# Tube_Board.net
KiCad netlist of a schematic drawn in EAGLE
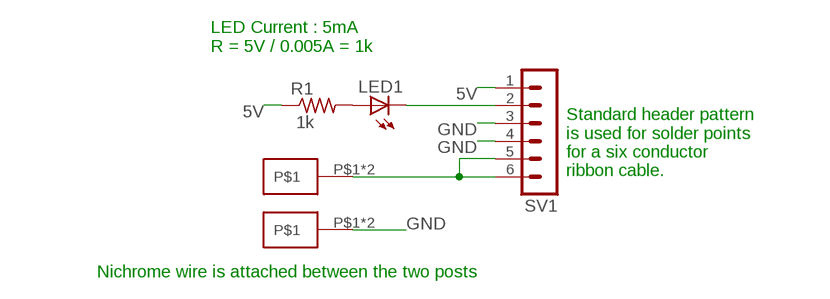
[diagram p0: schematic, sheet 1]

(export (version "E")
  (design (tool "Eeschema 10.0.6"))
  (components
    (comp (ref "LED1")
      (value "LED_ESML0603")
      (footprint "eagle-import:LED_SML0603")
      (libsource (lib "eagle-import") (part "LED_ESML0603"))
    )
    (comp (ref "R1")
      (value "R-US_R0603")
      (footprint "eagle-import:R0603")
      (fields (field (name "R1") "1k"))
      (libsource (lib "eagle-import") (part "R-US_R0603"))
    )
    (comp (ref "SV1")
      (value "MA06-1")
      (footprint "eagle-import:MA06-1")
      (libsource (lib "eagle-import") (part "MA06-1"))
    )
    (comp (ref "U$1")
      (value "A29938CT")
      (footprint "eagle-import:A29938CT")
      (libsource (lib "eagle-import") (part "A29938CT"))
    )
    (comp (ref "U$2")
      (value "A29938CT")
      (footprint "eagle-import:A29938CT")
      (libsource (lib "eagle-import") (part "A29938CT"))
    )
  )
  (nets
    (net (code "1") (name "/5V") (class "Default")
      (node (ref "R1") (pin "1") (pinfunction "1_1") (pintype "passive"))
      (node (ref "SV1") (pin "1") (pinfunction "1_1") (pintype "passive"))
    )
    (net (code "2") (name "/GND") (class "Default")
      (node (ref "SV1") (pin "3") (pinfunction "3_3") (pintype "passive"))
      (node (ref "SV1") (pin "4") (pinfunction "4_4") (pintype "passive"))
      (node (ref "U$2") (pin "P$1") (pinfunction "P$1_P$1") (pintype "bidirectional"))
      (node (ref "U$2") (pin "P$2") (pinfunction "P$1_P$2") (pintype "bidirectional"))
    )
    (net (code "3") (name "Net-(LED1-PadA)") (class "Default")
      (node (ref "LED1") (pin "A") (pinfunction "A_A") (pintype "passive"))
      (node (ref "R1") (pin "2") (pinfunction "2_2") (pintype "passive"))
    )
    (net (code "4") (name "Net-(LED1-PadC)") (class "Default")
      (node (ref "LED1") (pin "C") (pinfunction "C_C") (pintype "passive"))
      (node (ref "SV1") (pin "2") (pinfunction "2_2") (pintype "passive"))
    )
    (net (code "5") (name "Net-(SV1-Pad5)") (class "Default")
      (node (ref "SV1") (pin "5") (pinfunction "5_5") (pintype "passive"))
      (node (ref "SV1") (pin "6") (pinfunction "6_6") (pintype "passive"))
      (node (ref "U$1") (pin "P$1") (pinfunction "P$1_P$1") (pintype "bidirectional"))
      (node (ref "U$1") (pin "P$2") (pinfunction "P$1_P$2") (pintype "bidirectional"))
    )
  )
)
